# 08-I225-1.net
KiCad netlist of a schematic drawn in Altium Designer
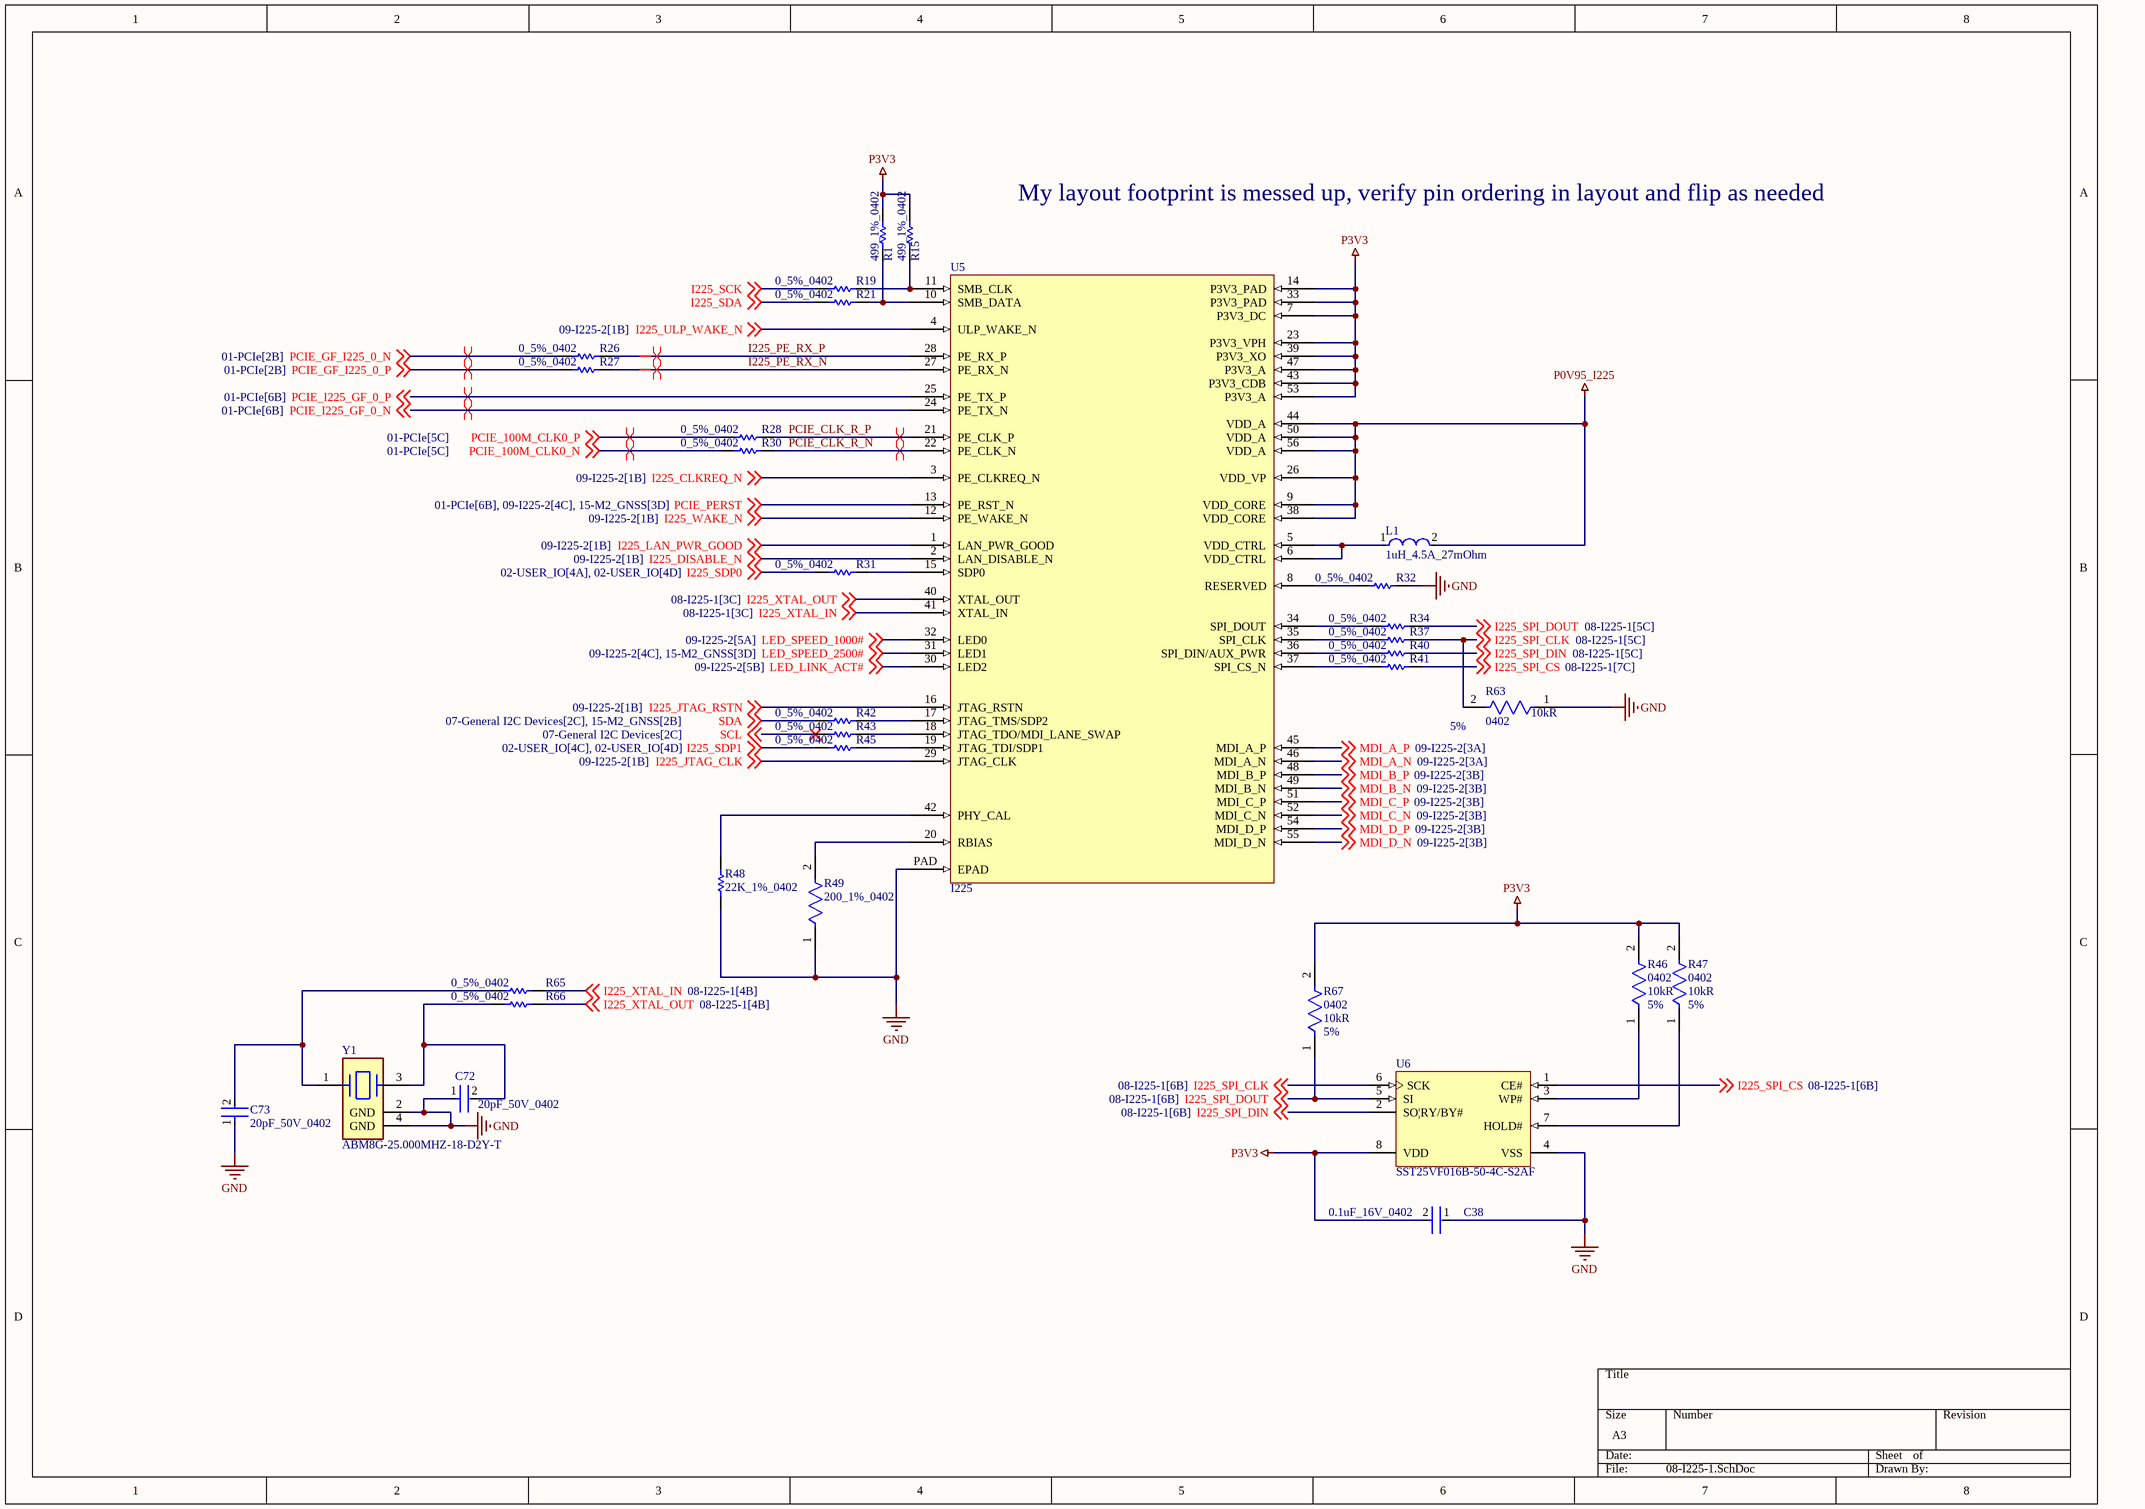
[diagram p0: 08-I225-1.SchDoc]

(export (version "E")
  (design (tool "Eeschema 10.0.6"))
  (components
    (comp (ref "C38")
      (value "0.1uF_16V_0402")
      (footprint "FP-GRM15-MFG")
      (description "CAP CER 0.1UF 16V X7R 0402")
      (fields (field (name "MANUFACTURER PART NUMBER") "GRM155R71C104KA88D") (field (name "TOLERANCE") "10%"))
      (libsource (lib "Altium Content Vault") (part "236180d848d6139a670b325ea6854c9"))
    )
    (comp (ref "C72")
      (value "20pF_50V_0402")
      (footprint "FP-C0402-BB-MFG")
      (description "CAP CER 20PF 50V 5% NP0 0402")
      (fields
        (field (name "MANUFACTURER PART NUMBER") "C0402C200J5GACTU")
        (field (name "OCTOPART") "https://octopart.com/c0402c200j5gactu-kemet-9143900")
      )
      (libsource (lib "Altium Content Vault") (part "b4654b650e69147ec39a6b967a45e02"))
    )
    (comp (ref "C73")
      (value "20pF_50V_0402")
      (footprint "FP-C0402-BB-MFG")
      (description "CAP CER 20PF 50V 5% NP0 0402")
      (fields
        (field (name "MANUFACTURER PART NUMBER") "C0402C200J5GACTU")
        (field (name "OCTOPART") "https://octopart.com/c0402c200j5gactu-kemet-9143900")
      )
      (libsource (lib "Altium Content Vault") (part "b4654b650e69147ec39a6b967a45e02"))
    )
    (comp (ref "L1")
      (value "1uH_4.5A_27mOhm")
      (footprint "FP-IHLP-1616BZ-FP_1_8545x-MFG")
      (description "Fixed Inductors Commercial Low DCR Series SMT 1uH 4.5A 27mΩ 20%")
      (fields (field (name "TOLERANCE") "20%"))
      (libsource (lib "Altium Content Vault") (part "725321dda6339637d4d059423bc1c3c"))
    )
    (comp (ref "R1")
      (value "499_1%_0402")
      (footprint "RESC1005X40X25LL05T05")
      (fields (field (name "MANUFACTURER") "Panasonic") (field (name "PART NUMBER") "ERJ-2RKF4990X"))
      (libsource (lib "Altium Content Vault") (part "RES"))
    )
    (comp (ref "R15")
      (value "499_1%_0402")
      (footprint "RESC1005X40X25LL05T05")
      (fields (field (name "MANUFACTURER") "Panasonic") (field (name "PART NUMBER") "ERJ-2RKF4990X"))
      (libsource (lib "Altium Content Vault") (part "RES"))
    )
    (comp (ref "R19")
      (value "0_5%_0402")
      (footprint "RESC1005X40X25LL10T10")
      (fields (field (name "MANUFACTURER") "KOA Speer") (field (name "PART NUMBER") "RK73Z1ETTP"))
      (libsource (lib "Altium Content Vault") (part "RES"))
    )
    (comp (ref "R21")
      (value "0_5%_0402")
      (footprint "RESC1005X40X25LL10T10")
      (fields (field (name "MANUFACTURER") "KOA Speer") (field (name "PART NUMBER") "RK73Z1ETTP"))
      (libsource (lib "Altium Content Vault") (part "RES"))
    )
    (comp (ref "R26")
      (value "0_5%_0402")
      (footprint "RESC1005X40X25LL10T10")
      (fields (field (name "MANUFACTURER") "KOA Speer") (field (name "PART NUMBER") "RK73Z1ETTP"))
      (libsource (lib "Altium Content Vault") (part "RES"))
    )
    (comp (ref "R27")
      (value "0_5%_0402")
      (footprint "RESC1005X40X25LL10T10")
      (fields (field (name "MANUFACTURER") "KOA Speer") (field (name "PART NUMBER") "RK73Z1ETTP"))
      (libsource (lib "Altium Content Vault") (part "RES"))
    )
    (comp (ref "R28")
      (value "0_5%_0402")
      (footprint "RESC1005X40X25LL10T10")
      (fields (field (name "MANUFACTURER") "KOA Speer") (field (name "PART NUMBER") "RK73Z1ETTP"))
      (libsource (lib "Altium Content Vault") (part "RES"))
    )
    (comp (ref "R30")
      (value "0_5%_0402")
      (footprint "RESC1005X40X25LL10T10")
      (fields (field (name "MANUFACTURER") "KOA Speer") (field (name "PART NUMBER") "RK73Z1ETTP"))
      (libsource (lib "Altium Content Vault") (part "RES"))
    )
    (comp (ref "R31")
      (value "0_5%_0402")
      (footprint "RESC1005X40X25LL10T10")
      (fields (field (name "MANUFACTURER") "KOA Speer") (field (name "PART NUMBER") "RK73Z1ETTP"))
      (libsource (lib "Altium Content Vault") (part "RES"))
    )
    (comp (ref "R32")
      (value "0_5%_0402")
      (footprint "RESC1005X40X25LL10T10")
      (fields (field (name "MANUFACTURER") "KOA Speer") (field (name "PART NUMBER") "RK73Z1ETTP"))
      (libsource (lib "Altium Content Vault") (part "RES"))
    )
    (comp (ref "R34")
      (value "0_5%_0402")
      (footprint "RESC1005X40X25LL10T10")
      (fields (field (name "MANUFACTURER") "KOA Speer") (field (name "PART NUMBER") "RK73Z1ETTP"))
      (libsource (lib "Altium Content Vault") (part "RES"))
    )
    (comp (ref "R37")
      (value "0_5%_0402")
      (footprint "RESC1005X40X25LL10T10")
      (fields (field (name "MANUFACTURER") "KOA Speer") (field (name "PART NUMBER") "RK73Z1ETTP"))
      (libsource (lib "Altium Content Vault") (part "RES"))
    )
    (comp (ref "R40")
      (value "0_5%_0402")
      (footprint "RESC1005X40X25LL10T10")
      (fields (field (name "MANUFACTURER") "KOA Speer") (field (name "PART NUMBER") "RK73Z1ETTP"))
      (libsource (lib "Altium Content Vault") (part "RES"))
    )
    (comp (ref "R41")
      (value "0_5%_0402")
      (footprint "RESC1005X40X25LL10T10")
      (fields (field (name "MANUFACTURER") "KOA Speer") (field (name "PART NUMBER") "RK73Z1ETTP"))
      (libsource (lib "Altium Content Vault") (part "RES"))
    )
    (comp (ref "R42")
      (value "0_5%_0402")
      (footprint "RESC1005X40X25LL10T10")
      (fields (field (name "MANUFACTURER") "KOA Speer") (field (name "PART NUMBER") "RK73Z1ETTP"))
      (libsource (lib "Altium Content Vault") (part "RES"))
    )
    (comp (ref "R43")
      (value "0_5%_0402")
      (footprint "RESC1005X40X25LL10T10")
      (fields (field (name "MANUFACTURER") "KOA Speer") (field (name "PART NUMBER") "RK73Z1ETTP"))
      (libsource (lib "Altium Content Vault") (part "RES"))
    )
    (comp (ref "R45")
      (value "0_5%_0402")
      (footprint "RESC1005X40X25LL10T10")
      (fields (field (name "MANUFACTURER") "KOA Speer") (field (name "PART NUMBER") "RK73Z1ETTP"))
      (libsource (lib "Altium Content Vault") (part "RES"))
    )
    (comp (ref "R46")
      (value "CRCW040210K0JNED")
      (footprint "FP-CRCW0402-e3-IPC_B")
      (description "RES Thick Film, 10kΩ, 5%, 0.063W, 200ppm/°C, 0402")
      (fields
        (field (name "CASE/PACKAGE") "0402")
        (field (name "RESISTANCE") "10kR")
        (field (name "TOLERANCE") "5%")
      )
      (libsource (lib "Altium Content Vault") (part "1029c3af85768c4190bb7ad29bc67b5"))
    )
    (comp (ref "R47")
      (value "CRCW040210K0JNED")
      (footprint "FP-CRCW0402-e3-IPC_B")
      (description "RES Thick Film, 10kΩ, 5%, 0.063W, 200ppm/°C, 0402")
      (fields
        (field (name "CASE/PACKAGE") "0402")
        (field (name "RESISTANCE") "10kR")
        (field (name "TOLERANCE") "5%")
      )
      (libsource (lib "Altium Content Vault") (part "1029c3af85768c4190bb7ad29bc67b5"))
    )
    (comp (ref "R48")
      (value "22K_1%_0402")
      (footprint "RESC1005X40X25NL05T05")
      (fields (field (name "PART NUMBER") "CRCW040222K0FKED") (field (name "MANUFACTURER") "Vishay Dale"))
      (libsource (lib "Altium Content Vault") (part "RES"))
    )
    (comp (ref "R49")
      (value "200_1%_0402")
      (footprint "FP-CRCW0402-e3-IPC_C")
      (description "RES Thick Film, 200Ω, 1%, 0.063W, 100ppm/°C, 0402")
      (fields (field (name "TOLERANCE") "1%"))
      (libsource (lib "Altium Content Vault") (part "1029c3af85768c4190bb7ad29bc67b5"))
    )
    (comp (ref "R63")
      (value "CRCW040210K0JNED")
      (footprint "FP-CRCW0402-e3-IPC_B")
      (description "RES Thick Film, 10kΩ, 5%, 0.063W, 200ppm/°C, 0402")
      (fields
        (field (name "CASE/PACKAGE") "0402")
        (field (name "RESISTANCE") "10kR")
        (field (name "TOLERANCE") "5%")
      )
      (libsource (lib "Altium Content Vault") (part "1029c3af85768c4190bb7ad29bc67b5"))
    )
    (comp (ref "R65")
      (value "0_5%_0402")
      (footprint "RESC1005X40X25LL10T10")
      (fields (field (name "MANUFACTURER") "KOA Speer") (field (name "PART NUMBER") "RK73Z1ETTP"))
      (libsource (lib "Altium Content Vault") (part "RES"))
    )
    (comp (ref "R66")
      (value "0_5%_0402")
      (footprint "RESC1005X40X25LL10T10")
      (fields (field (name "MANUFACTURER") "KOA Speer") (field (name "PART NUMBER") "RK73Z1ETTP"))
      (libsource (lib "Altium Content Vault") (part "RES"))
    )
    (comp (ref "R67")
      (value "CRCW040210K0JNED")
      (footprint "FP-CRCW0402-e3-IPC_B")
      (description "RES Thick Film, 10kΩ, 5%, 0.063W, 200ppm/°C, 0402")
      (fields
        (field (name "CASE/PACKAGE") "0402")
        (field (name "RESISTANCE") "10kR")
        (field (name "TOLERANCE") "5%")
      )
      (libsource (lib "Altium Content Vault") (part "1029c3af85768c4190bb7ad29bc67b5"))
    )
    (comp (ref "U5") (value "I225") (footprint "I225 QFN56") (libsource (lib "TimeStick_Lib") (part "I225")))
    (comp (ref "U6")
      (value "SST25VF016B-50-4C-S2AF")
      (footprint "MCHP-SOIC-S2A8_M")
      (description "16 Mbit SPI Serial Flash, 2.7 to 3.6 V, 50 MHz, 0 to 70 degC, 8-pin SOIC (S2A8), Tube")
      (fields (field (name "MANUFACTURER") "Microchip"))
      (libsource (lib "Altium Content Vault") (part "MCHP-SST25VFXXXB-SOIX-8"))
    )
    (comp (ref "Y1")
      (value "ABM8G-25.000MHZ-18-D2Y-T")
      (footprint "FP-ABM8G-MFG")
      (description "CRYSTAL 25.0000MHZ 18PF SMD")
      (fields
        (field (name "MANUFACTURER") "Abracon")
        (field (name "OCTOPART") "https://octopart.com/abm8g-25.000mhz-18-d2y-t-abracon-12676602")
      )
      (libsource (lib "Altium Content Vault") (part "82af6c543cb7a88a4cbd02a3a01c293"))
    )
  )
  (nets
    (net (code "1") (name "/I225_PE_RX_N") (class "Default")
      (node (ref "R27") (pin "2") (pinfunction "2_2") (pintype "passive"))
      (node (ref "U5") (pin "27") (pinfunction "PE_RX_N_27") (pintype "input"))
    )
    (net (code "2") (name "/I225_PE_RX_P") (class "Default")
      (node (ref "R26") (pin "2") (pinfunction "2_2") (pintype "passive"))
      (node (ref "U5") (pin "28") (pinfunction "PE_RX_P_28") (pintype "input"))
    )
    (net (code "3") (name "/PCIE_CLK_R_N") (class "Default")
      (node (ref "R30") (pin "2") (pinfunction "2_2") (pintype "passive"))
      (node (ref "U5") (pin "22") (pinfunction "PE_CLK_N_22") (pintype "input"))
    )
    (net (code "4") (name "/PCIE_CLK_R_P") (class "Default")
      (node (ref "R28") (pin "2") (pinfunction "2_2") (pintype "passive"))
      (node (ref "U5") (pin "21") (pinfunction "PE_CLK_P_21") (pintype "input"))
    )
    (net (code "5") (name "GND") (class "Default")
      (node (ref "C38") (pin "1") (pinfunction "1_1") (pintype "passive"))
      (node (ref "C72") (pin "1") (pinfunction "1_1") (pintype "passive"))
      (node (ref "C73") (pin "1") (pinfunction "1_1") (pintype "passive"))
      (node (ref "R32") (pin "2") (pinfunction "2_2") (pintype "passive"))
      (node (ref "R48") (pin "1") (pinfunction "1_1") (pintype "passive"))
      (node (ref "R49") (pin "1") (pinfunction "1_1") (pintype "passive"))
      (node (ref "R63") (pin "1") (pinfunction "1_1") (pintype "passive"))
      (node (ref "U5") (pin "PAD") (pinfunction "EPAD_PAD") (pintype "input"))
      (node (ref "U6") (pin "4") (pinfunction "VSS_4") (pintype "power_in"))
      (node (ref "Y1") (pin "2") (pinfunction "GND_2") (pintype "power_in"))
      (node (ref "Y1") (pin "4") (pinfunction "GND_4") (pintype "power_in"))
    )
    (net (code "6") (name "I225_CLKREQ_N") (class "Default")
      (node (ref "U5") (pin "3") (pinfunction "PE_CLKREQ_N_3") (pintype "input"))
    )
    (net (code "7") (name "I225_DISABLE_N") (class "Default")
      (node (ref "U5") (pin "2") (pinfunction "LAN_DISABLE_N_2") (pintype "input"))
    )
    (net (code "8") (name "I225_JTAG_CLK") (class "Default")
      (node (ref "U5") (pin "29") (pinfunction "JTAG_CLK_29") (pintype "input"))
    )
    (net (code "9") (name "I225_JTAG_RSTN") (class "Default")
      (node (ref "U5") (pin "16") (pinfunction "JTAG_RSTN_16") (pintype "input"))
    )
    (net (code "10") (name "I225_LAN_PWR_GOOD") (class "Default")
      (node (ref "U5") (pin "1") (pinfunction "LAN_PWR_GOOD_1") (pintype "input"))
    )
    (net (code "11") (name "I225_SCK") (class "Default")
      (node (ref "R19") (pin "1") (pinfunction "1_1") (pintype "passive"))
    )
    (net (code "12") (name "I225_SDA") (class "Default")
      (node (ref "R21") (pin "1") (pinfunction "1_1") (pintype "passive"))
    )
    (net (code "13") (name "I225_SDP0") (class "Default")
      (node (ref "R31") (pin "1") (pinfunction "1_1") (pintype "passive"))
    )
    (net (code "14") (name "I225_SDP1") (class "Default")
      (node (ref "R45") (pin "1") (pinfunction "1_1") (pintype "passive"))
    )
    (net (code "15") (name "I225_SPI_CLK") (class "Default")
      (node (ref "R37") (pin "2") (pinfunction "2_2") (pintype "passive"))
      (node (ref "R63") (pin "2") (pinfunction "2_2") (pintype "passive"))
      (node (ref "U6") (pin "6") (pinfunction "SCK_6") (pintype "input"))
    )
    (net (code "16") (name "I225_SPI_CS") (class "Default")
      (node (ref "R41") (pin "2") (pinfunction "2_2") (pintype "passive"))
      (node (ref "U6") (pin "1") (pinfunction "CE#_1") (pintype "input"))
    )
    (net (code "17") (name "I225_SPI_DIN") (class "Default")
      (node (ref "R40") (pin "2") (pinfunction "2_2") (pintype "passive"))
      (node (ref "U6") (pin "2") (pinfunction "SO¦RY/BY#_2") (pintype "tri_state"))
    )
    (net (code "18") (name "I225_SPI_DOUT") (class "Default")
      (node (ref "R34") (pin "2") (pinfunction "2_2") (pintype "passive"))
      (node (ref "R67") (pin "1") (pinfunction "1_1") (pintype "passive"))
      (node (ref "U6") (pin "5") (pinfunction "SI_5") (pintype "input"))
    )
    (net (code "19") (name "I225_ULP_WAKE_N") (class "Default")
      (node (ref "U5") (pin "4") (pinfunction "ULP_WAKE_N_4") (pintype "input"))
    )
    (net (code "20") (name "I225_WAKE_N") (class "Default")
      (node (ref "U5") (pin "12") (pinfunction "PE_WAKE_N_12") (pintype "input"))
    )
    (net (code "21") (name "I225_XTAL_IN") (class "Default")
      (node (ref "R65") (pin "2") (pinfunction "2_2") (pintype "passive"))
      (node (ref "U5") (pin "41") (pinfunction "XTAL_IN_41") (pintype "input"))
    )
    (net (code "22") (name "I225_XTAL_OUT") (class "Default")
      (node (ref "R66") (pin "2") (pinfunction "2_2") (pintype "passive"))
      (node (ref "U5") (pin "40") (pinfunction "XTAL_OUT_40") (pintype "input"))
    )
    (net (code "23") (name "LED_LINK_ACT#") (class "Default")
      (node (ref "U5") (pin "30") (pinfunction "LED2_30") (pintype "input"))
    )
    (net (code "24") (name "LED_SPEED_1000#") (class "Default")
      (node (ref "U5") (pin "32") (pinfunction "LED0_32") (pintype "input"))
    )
    (net (code "25") (name "LED_SPEED_2500#") (class "Default")
      (node (ref "U5") (pin "31") (pinfunction "LED1_31") (pintype "input"))
    )
    (net (code "26") (name "MDI_A_N") (class "Default")
      (node (ref "U5") (pin "46") (pinfunction "MDI_A_N_46") (pintype "input"))
    )
    (net (code "27") (name "MDI_A_P") (class "Default")
      (node (ref "U5") (pin "45") (pinfunction "MDI_A_P_45") (pintype "input"))
    )
    (net (code "28") (name "MDI_B_N") (class "Default")
      (node (ref "U5") (pin "49") (pinfunction "MDI_B_N_49") (pintype "input"))
    )
    (net (code "29") (name "MDI_B_P") (class "Default")
      (node (ref "U5") (pin "48") (pinfunction "MDI_B_P_48") (pintype "input"))
    )
    (net (code "30") (name "MDI_C_N") (class "Default")
      (node (ref "U5") (pin "52") (pinfunction "MDI_C_N_52") (pintype "input"))
    )
    (net (code "31") (name "MDI_C_P") (class "Default")
      (node (ref "U5") (pin "51") (pinfunction "MDI_C_P_51") (pintype "input"))
    )
    (net (code "32") (name "MDI_D_N") (class "Default")
      (node (ref "U5") (pin "55") (pinfunction "MDI_D_N_55") (pintype "input"))
    )
    (net (code "33") (name "MDI_D_P") (class "Default")
      (node (ref "U5") (pin "54") (pinfunction "MDI_D_P_54") (pintype "input"))
    )
    (net (code "34") (name "Net-(C72-Pad2)") (class "Default")
      (node (ref "C72") (pin "2") (pinfunction "2_2") (pintype "passive"))
      (node (ref "R66") (pin "1") (pinfunction "1_1") (pintype "passive"))
      (node (ref "Y1") (pin "3") (pinfunction "3_3") (pintype "passive"))
    )
    (net (code "35") (name "Net-(C73-Pad2)") (class "Default")
      (node (ref "C73") (pin "2") (pinfunction "2_2") (pintype "passive"))
      (node (ref "R65") (pin "1") (pinfunction "1_1") (pintype "passive"))
      (node (ref "Y1") (pin "1") (pinfunction "1_1") (pintype "passive"))
    )
    (net (code "36") (name "Net-(L1-Pad1)") (class "Default")
      (node (ref "L1") (pin "1") (pinfunction "1_1") (pintype "passive"))
      (node (ref "U5") (pin "5") (pinfunction "VDD_CTRL_5") (pintype "input"))
      (node (ref "U5") (pin "6") (pinfunction "VDD_CTRL_6") (pintype "input"))
    )
    (net (code "37") (name "Net-(U5-JTAG_TDI{slash}SDP1)") (class "Default")
      (node (ref "R45") (pin "2") (pinfunction "2_2") (pintype "passive"))
      (node (ref "U5") (pin "19") (pinfunction "JTAG_TDI/SDP1_19") (pintype "input"))
    )
    (net (code "38") (name "Net-(U5-JTAG_TDO{slash}MDI_LANE_SWAP)") (class "Default")
      (node (ref "R43") (pin "2") (pinfunction "2_2") (pintype "passive"))
      (node (ref "U5") (pin "18") (pinfunction "JTAG_TDO/MDI_LANE_SWAP_18") (pintype "input"))
    )
    (net (code "39") (name "Net-(U5-JTAG_TMS{slash}SDP2)") (class "Default")
      (node (ref "R42") (pin "2") (pinfunction "2_2") (pintype "passive"))
      (node (ref "U5") (pin "17") (pinfunction "JTAG_TMS/SDP2_17") (pintype "input"))
    )
    (net (code "40") (name "Net-(U5-PHY_CAL)") (class "Default")
      (node (ref "R48") (pin "2") (pinfunction "2_2") (pintype "passive"))
      (node (ref "U5") (pin "42") (pinfunction "PHY_CAL_42") (pintype "input"))
    )
    (net (code "41") (name "Net-(U5-RBIAS)") (class "Default")
      (node (ref "R49") (pin "2") (pinfunction "2_2") (pintype "passive"))
      (node (ref "U5") (pin "20") (pinfunction "RBIAS_20") (pintype "input"))
    )
    (net (code "42") (name "Net-(U5-RESERVED)") (class "Default")
      (node (ref "R32") (pin "1") (pinfunction "1_1") (pintype "passive"))
      (node (ref "U5") (pin "8") (pinfunction "RESERVED_8") (pintype "input"))
    )
    (net (code "43") (name "Net-(U5-SDP0)") (class "Default")
      (node (ref "R31") (pin "2") (pinfunction "2_2") (pintype "passive"))
      (node (ref "U5") (pin "15") (pinfunction "SDP0_15") (pintype "input"))
    )
    (net (code "44") (name "Net-(U5-SMB_CLK)") (class "Default")
      (node (ref "R15") (pin "1") (pinfunction "1_1") (pintype "passive"))
      (node (ref "R19") (pin "2") (pinfunction "2_2") (pintype "passive"))
      (node (ref "U5") (pin "11") (pinfunction "SMB_CLK_11") (pintype "input"))
    )
    (net (code "45") (name "Net-(U5-SMB_DATA)") (class "Default")
      (node (ref "R1") (pin "1") (pinfunction "1_1") (pintype "passive"))
      (node (ref "R21") (pin "2") (pinfunction "2_2") (pintype "passive"))
      (node (ref "U5") (pin "10") (pinfunction "SMB_DATA_10") (pintype "input"))
    )
    (net (code "46") (name "Net-(U5-SPI_CLK)") (class "Default")
      (node (ref "R37") (pin "1") (pinfunction "1_1") (pintype "passive"))
      (node (ref "U5") (pin "35") (pinfunction "SPI_CLK_35") (pintype "input"))
    )
    (net (code "47") (name "Net-(U5-SPI_CS_N)") (class "Default")
      (node (ref "R41") (pin "1") (pinfunction "1_1") (pintype "passive"))
      (node (ref "U5") (pin "37") (pinfunction "SPI_CS_N_37") (pintype "input"))
    )
    (net (code "48") (name "Net-(U5-SPI_DIN{slash}AUX_PWR)") (class "Default")
      (node (ref "R40") (pin "1") (pinfunction "1_1") (pintype "passive"))
      (node (ref "U5") (pin "36") (pinfunction "SPI_DIN/AUX_PWR_36") (pintype "input"))
    )
    (net (code "49") (name "Net-(U5-SPI_DOUT)") (class "Default")
      (node (ref "R34") (pin "1") (pinfunction "1_1") (pintype "passive"))
      (node (ref "U5") (pin "34") (pinfunction "SPI_DOUT_34") (pintype "input"))
    )
    (net (code "50") (name "Net-(U6-HOLD#)") (class "Default")
      (node (ref "R47") (pin "1") (pinfunction "1_1") (pintype "passive"))
      (node (ref "U6") (pin "7") (pinfunction "HOLD#_7") (pintype "input"))
    )
    (net (code "51") (name "Net-(U6-WP#)") (class "Default")
      (node (ref "R46") (pin "1") (pinfunction "1_1") (pintype "passive"))
      (node (ref "U6") (pin "3") (pinfunction "WP#_3") (pintype "input"))
    )
    (net (code "52") (name "P0V95_I225") (class "Default")
      (node (ref "L1") (pin "2") (pinfunction "2_2") (pintype "passive"))
      (node (ref "U5") (pin "26") (pinfunction "VDD_VP_26") (pintype "input"))
      (node (ref "U5") (pin "38") (pinfunction "VDD_CORE_38") (pintype "input"))
      (node (ref "U5") (pin "44") (pinfunction "VDD_A_44") (pintype "input"))
      (node (ref "U5") (pin "50") (pinfunction "VDD_A_50") (pintype "input"))
      (node (ref "U5") (pin "56") (pinfunction "VDD_A_56") (pintype "input"))
      (node (ref "U5") (pin "9") (pinfunction "VDD_CORE_9") (pintype "input"))
    )
    (net (code "53") (name "P3V3") (class "Default")
      (node (ref "C38") (pin "2") (pinfunction "2_2") (pintype "passive"))
      (node (ref "R1") (pin "2") (pinfunction "2_2") (pintype "passive"))
      (node (ref "R15") (pin "2") (pinfunction "2_2") (pintype "passive"))
      (node (ref "R46") (pin "2") (pinfunction "2_2") (pintype "passive"))
      (node (ref "R47") (pin "2") (pinfunction "2_2") (pintype "passive"))
      (node (ref "R67") (pin "2") (pinfunction "2_2") (pintype "passive"))
      (node (ref "U5") (pin "14") (pinfunction "P3V3_PAD_14") (pintype "input"))
      (node (ref "U5") (pin "23") (pinfunction "P3V3_VPH_23") (pintype "input"))
      (node (ref "U5") (pin "33") (pinfunction "P3V3_PAD_33") (pintype "input"))
      (node (ref "U5") (pin "39") (pinfunction "P3V3_XO_39") (pintype "input"))
      (node (ref "U5") (pin "43") (pinfunction "P3V3_CDB_43") (pintype "input"))
      (node (ref "U5") (pin "47") (pinfunction "P3V3_A_47") (pintype "input"))
      (node (ref "U5") (pin "53") (pinfunction "P3V3_A_53") (pintype "input"))
      (node (ref "U5") (pin "7") (pinfunction "P3V3_DC_7") (pintype "input"))
      (node (ref "U6") (pin "8") (pinfunction "VDD_8") (pintype "power_in"))
    )
    (net (code "54") (name "PCIE_100M_CLK0_N") (class "Default")
      (node (ref "R30") (pin "1") (pinfunction "1_1") (pintype "passive"))
    )
    (net (code "55") (name "PCIE_100M_CLK0_P") (class "Default")
      (node (ref "R28") (pin "1") (pinfunction "1_1") (pintype "passive"))
    )
    (net (code "56") (name "PCIE_GF_I225_0_N") (class "Default")
      (node (ref "R26") (pin "1") (pinfunction "1_1") (pintype "passive"))
    )
    (net (code "57") (name "PCIE_GF_I225_0_P") (class "Default")
      (node (ref "R27") (pin "1") (pinfunction "1_1") (pintype "passive"))
    )
    (net (code "58") (name "PCIE_I225_GF_0_N") (class "Default")
      (node (ref "U5") (pin "24") (pinfunction "PE_TX_N_24") (pintype "input"))
    )
    (net (code "59") (name "PCIE_I225_GF_0_P") (class "Default")
      (node (ref "U5") (pin "25") (pinfunction "PE_TX_P_25") (pintype "input"))
    )
    (net (code "60") (name "PCIE_PERST") (class "Default")
      (node (ref "U5") (pin "13") (pinfunction "PE_RST_N_13") (pintype "input"))
    )
    (net (code "61") (name "SCL") (class "Default")
      (node (ref "R43") (pin "1") (pinfunction "1_1") (pintype "passive"))
    )
    (net (code "62") (name "SDA") (class "Default")
      (node (ref "R42") (pin "1") (pinfunction "1_1") (pintype "passive"))
    )
  )
)
